# Grove_-_Gesture_v1_0.net
KiCad netlist of a schematic drawn in EAGLE
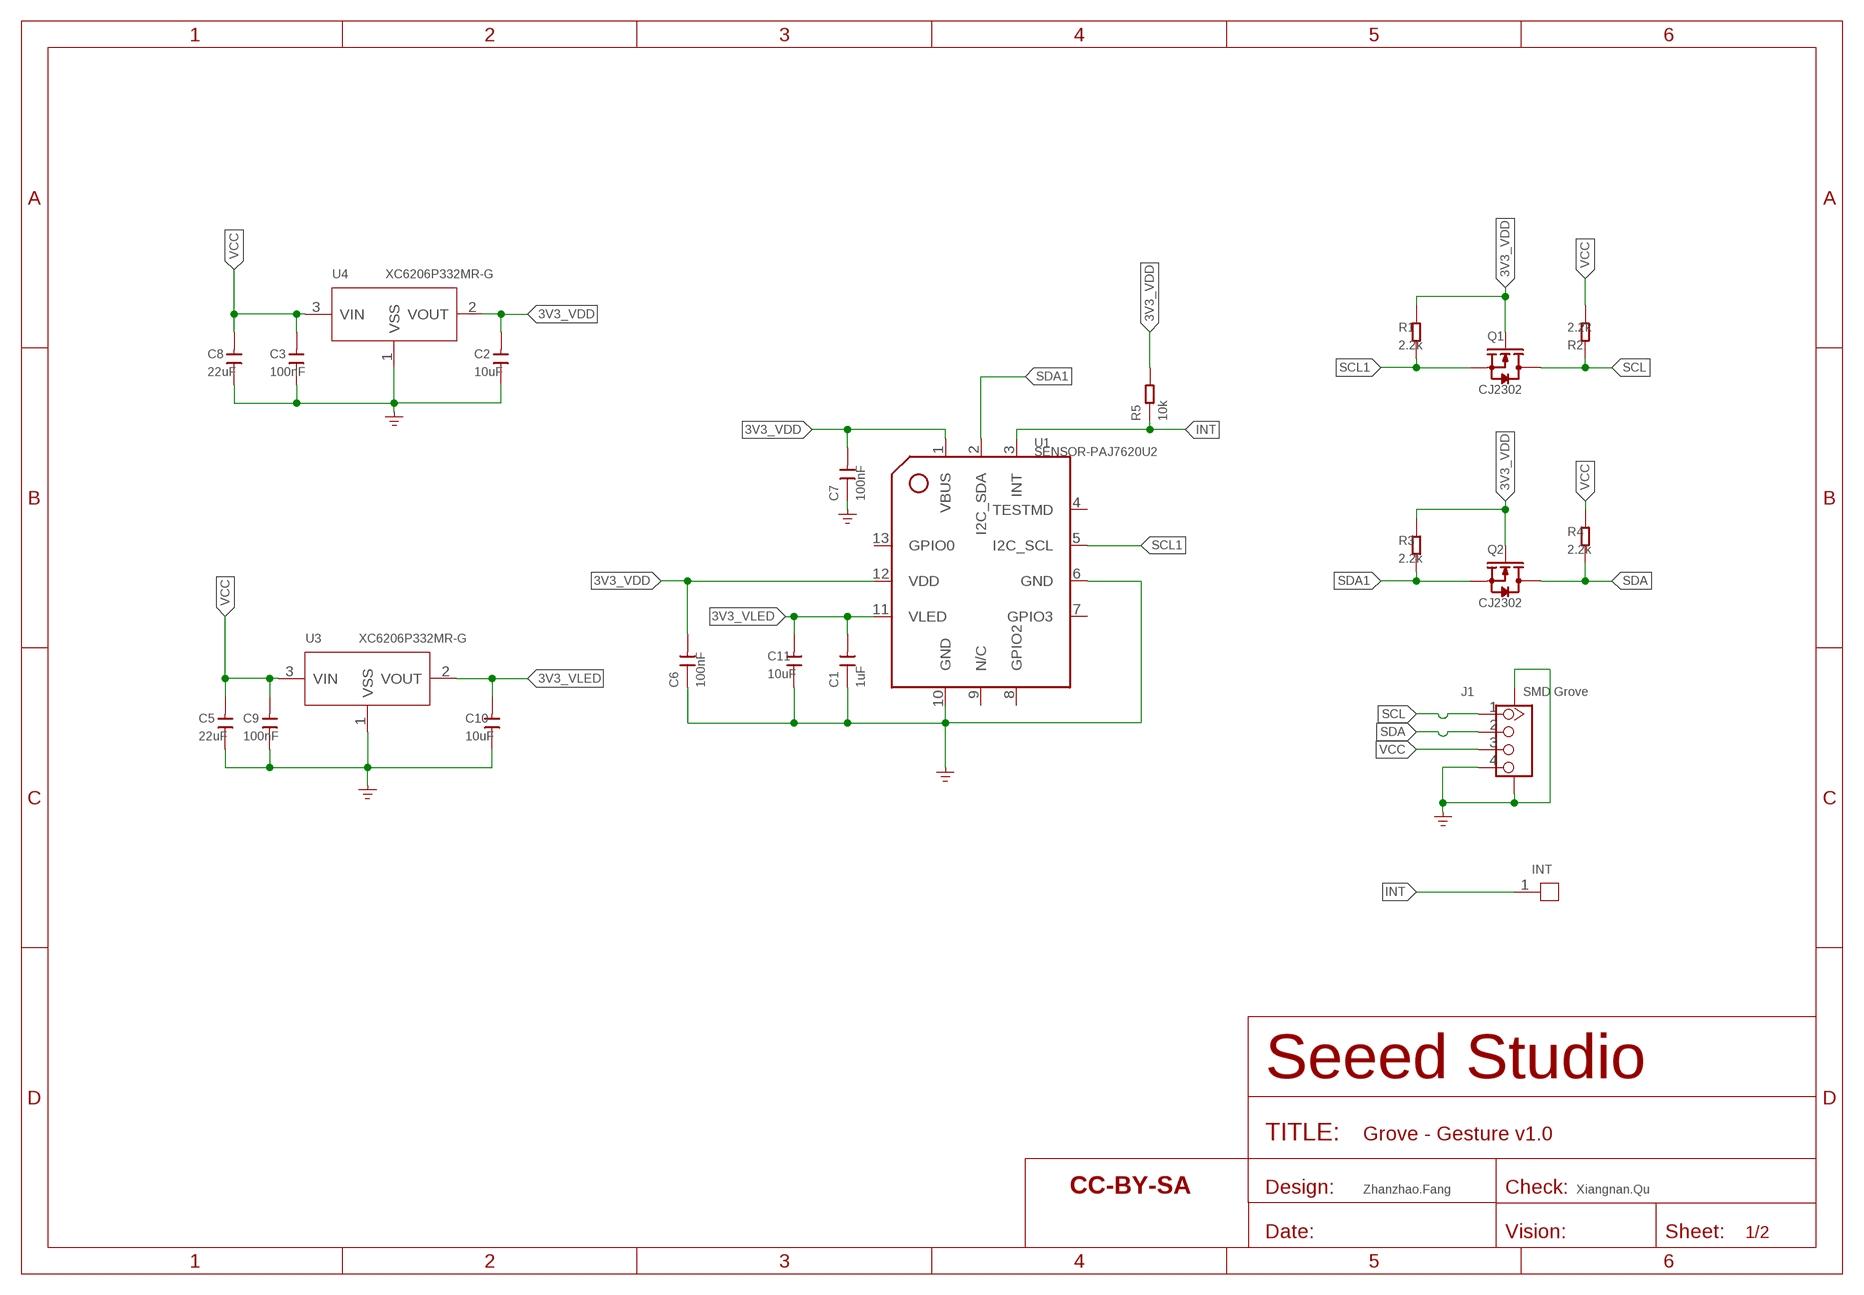
[diagram p0: schematic, sheet 1]
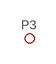
[diagram p1: schematic, sheet 2]

(export (version "E")
  (design (tool "Eeschema 10.0.6"))
  (components
    (comp (ref "P3")
      (value "PAD-MARK'ANNULAR'")
      (footprint "eagle-import:ROUND-MARK-1.0")
      (fields (field (name "PARTNO") "DNP"))
      (libsource (lib "eagle-import") (part "PAD-MARK'ANNULAR'"))
    )
    (comp (ref "C1")
      (value "1uF")
      (footprint "eagle-import:C0603")
      (libsource (lib "eagle-import") (part "CAP-0603"))
    )
    (comp (ref "C2")
      (value "10uF")
      (footprint "eagle-import:C0603")
      (libsource (lib "eagle-import") (part "CAP-0603"))
    )
    (comp (ref "C3")
      (value "100nF")
      (footprint "eagle-import:C0603")
      (libsource (lib "eagle-import") (part "CAP-0603"))
    )
    (comp (ref "C5")
      (value "22uF")
      (footprint "eagle-import:C0805")
      (libsource (lib "eagle-import") (part "CAP-0805"))
    )
    (comp (ref "C6")
      (value "100nF")
      (footprint "eagle-import:C0603")
      (libsource (lib "eagle-import") (part "CAP-0603"))
    )
    (comp (ref "C7")
      (value "100nF")
      (footprint "eagle-import:C0603")
      (libsource (lib "eagle-import") (part "CAP-0603"))
    )
    (comp (ref "C8")
      (value "22uF")
      (footprint "eagle-import:C0805")
      (libsource (lib "eagle-import") (part "CAP-0805"))
    )
    (comp (ref "C9")
      (value "100nF")
      (footprint "eagle-import:C0603")
      (libsource (lib "eagle-import") (part "CAP-0603"))
    )
    (comp (ref "C10")
      (value "10uF")
      (footprint "eagle-import:C0603")
      (libsource (lib "eagle-import") (part "CAP-0603"))
    )
    (comp (ref "C11")
      (value "10uF")
      (footprint "eagle-import:C0603")
      (libsource (lib "eagle-import") (part "CAP-0603"))
    )
    (comp (ref "INT")
      (value "DNP")
      (footprint "eagle-import:1P-80_40MIL")
      (libsource (lib "eagle-import") (part "HEADER-1P-40"))
    )
    (comp (ref "J1")
      (value "SMD Grove")
      (footprint "eagle-import:HW4-SMD-2.0-90D")
      (libsource (lib "eagle-import") (part "GROVE-CONNECTOR-SMD'90D'"))
    )
    (comp (ref "Q1")
      (value "CJ2302")
      (footprint "eagle-import:SOT-23")
      (libsource (lib "eagle-import") (part "MOSFET-N'SOT23'"))
    )
    (comp (ref "Q2")
      (value "CJ2302")
      (footprint "eagle-import:SOT-23")
      (libsource (lib "eagle-import") (part "MOSFET-N'SOT23'"))
    )
    (comp (ref "R1")
      (value "2.2k")
      (footprint "eagle-import:R0603")
      (libsource (lib "eagle-import") (part "RES-0603"))
    )
    (comp (ref "R2")
      (value "2.2k")
      (footprint "eagle-import:R0603")
      (libsource (lib "eagle-import") (part "RES-0603"))
    )
    (comp (ref "R3")
      (value "2.2k")
      (footprint "eagle-import:R0603")
      (libsource (lib "eagle-import") (part "RES-0603"))
    )
    (comp (ref "R4")
      (value "2.2k")
      (footprint "eagle-import:R0603")
      (libsource (lib "eagle-import") (part "RES-0603"))
    )
    (comp (ref "R5")
      (value "10k")
      (footprint "eagle-import:R0603")
      (libsource (lib "eagle-import") (part "RES-0603"))
    )
    (comp (ref "U$4")
      (value "SEEEDSTUDIO-OPEN-SCH-FRAME")
      (footprint "eagle-import:SEEEDSTUDIO-PCB-FRAME")
      (libsource (lib "eagle-import") (part "SEEEDSTUDIO-OPEN-SCH-FRAME"))
    )
    (comp (ref "U1")
      (value "SENSOR-PAJ7620U2")
      (footprint "eagle-import:LGA13-SMD-L5.2_W3_H2MM")
      (libsource (lib "eagle-import") (part "SENSOR-PAJ7620U2"))
    )
    (comp (ref "U3")
      (value "XC6206P332MR-G")
      (footprint "eagle-import:SOT-23")
      (libsource (lib "eagle-import") (part "PMIC-XC6206PMR"))
    )
    (comp (ref "U4")
      (value "XC6206P332MR-G")
      (footprint "eagle-import:SOT-23")
      (libsource (lib "eagle-import") (part "PMIC-XC6206PMR"))
    )
  )
  (nets
    (net (code "1") (name "3V3_VDD") (class "Default")
      (node (ref "C2") (pin "2") (pinfunction "2_2") (pintype "passive"))
      (node (ref "C6") (pin "2") (pinfunction "2_2") (pintype "passive"))
      (node (ref "C7") (pin "2") (pinfunction "2_2") (pintype "passive"))
      (node (ref "Q1") (pin "1") (pinfunction "G_1") (pintype "passive"))
      (node (ref "Q2") (pin "1") (pinfunction "G_1") (pintype "passive"))
      (node (ref "R1") (pin "2") (pinfunction "2_2") (pintype "passive"))
      (node (ref "R3") (pin "2") (pinfunction "2_2") (pintype "passive"))
      (node (ref "R5") (pin "2") (pinfunction "2_2") (pintype "passive"))
      (node (ref "U1") (pin "1") (pinfunction "VBUS_1") (pintype "bidirectional"))
      (node (ref "U1") (pin "12") (pinfunction "VDD_12") (pintype "bidirectional"))
      (node (ref "U4") (pin "2") (pinfunction "VOUT_2") (pintype "output"))
    )
    (net (code "2") (name "3V3_VLED") (class "Default")
      (node (ref "C1") (pin "2") (pinfunction "2_2") (pintype "passive"))
      (node (ref "C10") (pin "2") (pinfunction "2_2") (pintype "passive"))
      (node (ref "C11") (pin "2") (pinfunction "2_2") (pintype "passive"))
      (node (ref "U1") (pin "11") (pinfunction "VLED_11") (pintype "bidirectional"))
      (node (ref "U3") (pin "2") (pinfunction "VOUT_2") (pintype "output"))
    )
    (net (code "3") (name "GND") (class "Default")
      (node (ref "C1") (pin "1") (pinfunction "1_1") (pintype "passive"))
      (node (ref "C10") (pin "1") (pinfunction "1_1") (pintype "passive"))
      (node (ref "C11") (pin "1") (pinfunction "1_1") (pintype "passive"))
      (node (ref "C2") (pin "1") (pinfunction "1_1") (pintype "passive"))
      (node (ref "C3") (pin "1") (pinfunction "1_1") (pintype "passive"))
      (node (ref "C5") (pin "1") (pinfunction "1_1") (pintype "passive"))
      (node (ref "C6") (pin "1") (pinfunction "1_1") (pintype "passive"))
      (node (ref "C7") (pin "1") (pinfunction "1_1") (pintype "passive"))
      (node (ref "C8") (pin "1") (pinfunction "1_1") (pintype "passive"))
      (node (ref "C9") (pin "1") (pinfunction "1_1") (pintype "passive"))
      (node (ref "J1") (pin "4") (pinfunction "4_4") (pintype "bidirectional"))
      (node (ref "J1") (pin "SS1") (pinfunction "SS1_SS1") (pintype "bidirectional"))
      (node (ref "J1") (pin "SS2") (pinfunction "SS2_SS2") (pintype "bidirectional"))
      (node (ref "U1") (pin "10") (pinfunction "GND_10") (pintype "bidirectional"))
      (node (ref "U1") (pin "6") (pinfunction "GND_6") (pintype "bidirectional"))
      (node (ref "U3") (pin "1") (pinfunction "VSS_1") (pintype "power_in"))
      (node (ref "U4") (pin "1") (pinfunction "VSS_1") (pintype "power_in"))
    )
    (net (code "4") (name "INT") (class "Default")
      (node (ref "INT") (pin "1") (pinfunction "1_1") (pintype "bidirectional"))
      (node (ref "R5") (pin "1") (pinfunction "1_1") (pintype "passive"))
      (node (ref "U1") (pin "3") (pinfunction "INT_3") (pintype "bidirectional"))
    )
    (net (code "5") (name "SCL") (class "Default")
      (node (ref "J1") (pin "1") (pinfunction "1_1") (pintype "bidirectional"))
      (node (ref "Q1") (pin "3") (pinfunction "D_3") (pintype "passive"))
      (node (ref "R2") (pin "1") (pinfunction "1_1") (pintype "passive"))
    )
    (net (code "6") (name "SCL1") (class "Default")
      (node (ref "Q1") (pin "2") (pinfunction "S_2") (pintype "passive"))
      (node (ref "R1") (pin "1") (pinfunction "1_1") (pintype "passive"))
      (node (ref "U1") (pin "5") (pinfunction "I2C_SCL_5") (pintype "bidirectional"))
    )
    (net (code "7") (name "SDA") (class "Default")
      (node (ref "J1") (pin "2") (pinfunction "2_2") (pintype "bidirectional"))
      (node (ref "Q2") (pin "3") (pinfunction "D_3") (pintype "passive"))
      (node (ref "R4") (pin "1") (pinfunction "1_1") (pintype "passive"))
    )
    (net (code "8") (name "SDA1") (class "Default")
      (node (ref "Q2") (pin "2") (pinfunction "S_2") (pintype "passive"))
      (node (ref "R3") (pin "1") (pinfunction "1_1") (pintype "passive"))
      (node (ref "U1") (pin "2") (pinfunction "I2C_SDA_2") (pintype "bidirectional"))
    )
    (net (code "9") (name "VCC") (class "Default")
      (node (ref "C3") (pin "2") (pinfunction "2_2") (pintype "passive"))
      (node (ref "C5") (pin "2") (pinfunction "2_2") (pintype "passive"))
      (node (ref "C8") (pin "2") (pinfunction "2_2") (pintype "passive"))
      (node (ref "C9") (pin "2") (pinfunction "2_2") (pintype "passive"))
      (node (ref "J1") (pin "3") (pinfunction "3_3") (pintype "bidirectional"))
      (node (ref "R2") (pin "2") (pinfunction "2_2") (pintype "passive"))
      (node (ref "R4") (pin "2") (pinfunction "2_2") (pintype "passive"))
      (node (ref "U3") (pin "3") (pinfunction "VIN_3") (pintype "input"))
      (node (ref "U4") (pin "3") (pinfunction "VIN_3") (pintype "input"))
    )
    (net (code "10") (name "unconnected-(U1-GPIO0-Pad13)") (class "Default")
      (node (ref "U1") (pin "13") (pinfunction "GPIO0_13") (pintype "bidirectional"))
    )
    (net (code "11") (name "unconnected-(U1-GPIO2-Pad8)") (class "Default")
      (node (ref "U1") (pin "8") (pinfunction "GPIO2_8") (pintype "bidirectional"))
    )
    (net (code "12") (name "unconnected-(U1-GPIO3-Pad7)") (class "Default")
      (node (ref "U1") (pin "7") (pinfunction "GPIO3_7") (pintype "bidirectional"))
    )
    (net (code "13") (name "unconnected-(U1-N{slash}C-Pad9)") (class "Default")
      (node (ref "U1") (pin "9") (pinfunction "N/C_9") (pintype "bidirectional"))
    )
    (net (code "14") (name "unconnected-(U1-TESTMD-Pad4)") (class "Default")
      (node (ref "U1") (pin "4") (pinfunction "TESTMD_4") (pintype "bidirectional"))
    )
  )
)
